# Temp_Board_1_2_2.net
KiCad netlist of a schematic drawn in EAGLE
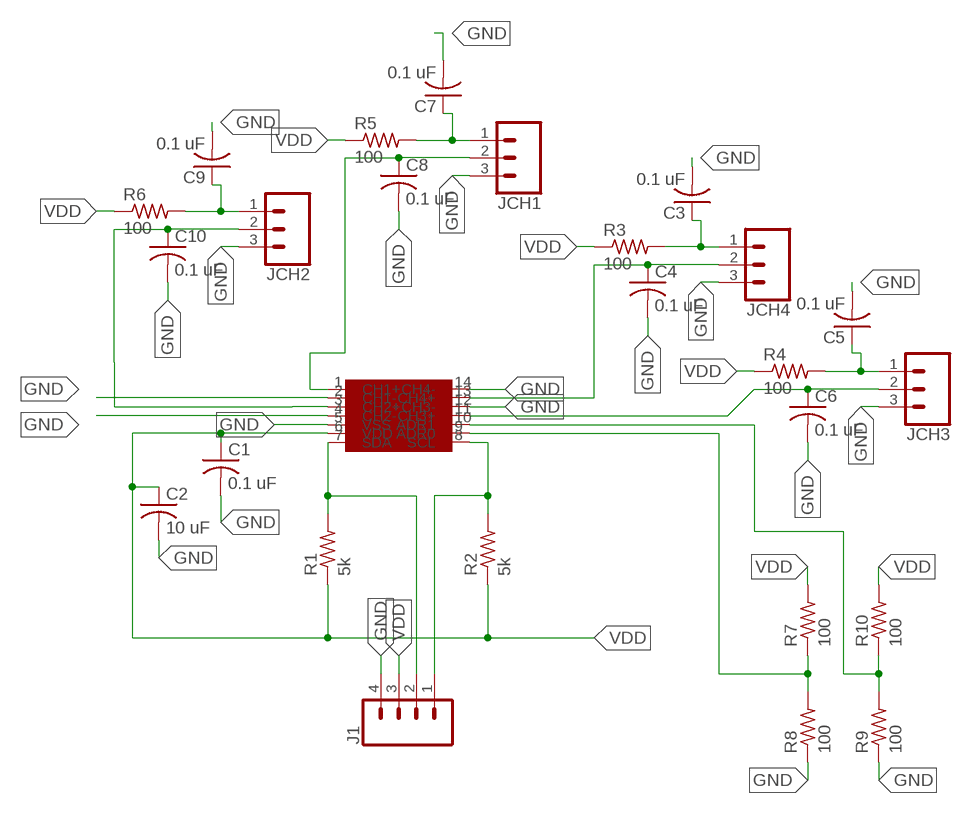
[diagram p0: schematic, sheet 1]

(export (version "E")
  (design (tool "Eeschema 10.0.6"))
  (components
    (comp (ref "C1")
      (value "0.1 uF")
      (footprint "eagle-import:C0805")
      (libsource (lib "eagle-import") (part "C-USC0805"))
    )
    (comp (ref "C2")
      (value "10 uF")
      (footprint "eagle-import:C0805")
      (libsource (lib "eagle-import") (part "C-USC0805"))
    )
    (comp (ref "C3")
      (value "0.1 uF")
      (footprint "eagle-import:C0805")
      (libsource (lib "eagle-import") (part "C-USC0805"))
    )
    (comp (ref "C4")
      (value "0.1 uF")
      (footprint "eagle-import:C0805")
      (libsource (lib "eagle-import") (part "C-USC0805"))
    )
    (comp (ref "C5")
      (value "0.1 uF")
      (footprint "eagle-import:C0805")
      (libsource (lib "eagle-import") (part "C-USC0805"))
    )
    (comp (ref "C6")
      (value "0.1 uF")
      (footprint "eagle-import:C0805")
      (libsource (lib "eagle-import") (part "C-USC0805"))
    )
    (comp (ref "C7")
      (value "0.1 uF")
      (footprint "eagle-import:C0805")
      (libsource (lib "eagle-import") (part "C-USC0805"))
    )
    (comp (ref "C8")
      (value "0.1 uF")
      (footprint "eagle-import:C0805")
      (libsource (lib "eagle-import") (part "C-USC0805"))
    )
    (comp (ref "C9")
      (value "0.1 uF")
      (footprint "eagle-import:C0805")
      (libsource (lib "eagle-import") (part "C-USC0805"))
    )
    (comp (ref "C10")
      (value "0.1 uF")
      (footprint "eagle-import:C0805")
      (libsource (lib "eagle-import") (part "C-USC0805"))
    )
    (comp (ref "J1")
      (value "CONN_04LOCK_LONGPADS")
      (footprint "eagle-import:1X04_LOCK_LONGPADS")
      (libsource (lib "eagle-import") (part "CONN_04LOCK_LONGPADS"))
    )
    (comp (ref "JCH1")
      (value "CONN_03LOCK_LONGPADS")
      (footprint "eagle-import:1X03_LOCK_LONGPADS")
      (libsource (lib "eagle-import") (part "CONN_03LOCK_LONGPADS"))
    )
    (comp (ref "JCH2")
      (value "CONN_03LOCK_LONGPADS")
      (footprint "eagle-import:1X03_LOCK_LONGPADS")
      (libsource (lib "eagle-import") (part "CONN_03LOCK_LONGPADS"))
    )
    (comp (ref "JCH3")
      (value "CONN_03LOCK_LONGPADS")
      (footprint "eagle-import:1X03_LOCK_LONGPADS")
      (libsource (lib "eagle-import") (part "CONN_03LOCK_LONGPADS"))
    )
    (comp (ref "JCH4")
      (value "CONN_03LOCK_LONGPADS")
      (footprint "eagle-import:1X03_LOCK_LONGPADS")
      (libsource (lib "eagle-import") (part "CONN_03LOCK_LONGPADS"))
    )
    (comp (ref "R1")
      (value "5k")
      (footprint "eagle-import:M0805")
      (libsource (lib "eagle-import") (part "R-US_M0805"))
    )
    (comp (ref "R2")
      (value "5k")
      (footprint "eagle-import:M0805")
      (libsource (lib "eagle-import") (part "R-US_M0805"))
    )
    (comp (ref "R3")
      (value "100")
      (footprint "eagle-import:M0805")
      (libsource (lib "eagle-import") (part "R-US_M0805"))
    )
    (comp (ref "R4")
      (value "100")
      (footprint "eagle-import:M0805")
      (libsource (lib "eagle-import") (part "R-US_M0805"))
    )
    (comp (ref "R5")
      (value "100")
      (footprint "eagle-import:M0805")
      (libsource (lib "eagle-import") (part "R-US_M0805"))
    )
    (comp (ref "R6")
      (value "100")
      (footprint "eagle-import:M0805")
      (libsource (lib "eagle-import") (part "R-US_M0805"))
    )
    (comp (ref "R7")
      (value "100")
      (footprint "eagle-import:M0805")
      (libsource (lib "eagle-import") (part "R-US_M0805"))
    )
    (comp (ref "R8")
      (value "100")
      (footprint "eagle-import:M0805")
      (libsource (lib "eagle-import") (part "R-US_M0805"))
    )
    (comp (ref "R9")
      (value "100")
      (footprint "eagle-import:M0805")
      (libsource (lib "eagle-import") (part "R-US_M0805"))
    )
    (comp (ref "R10")
      (value "100")
      (footprint "eagle-import:M0805")
      (libsource (lib "eagle-import") (part "R-US_M0805"))
    )
    (comp (ref "U$1")
      (value "MCP3428A")
      (footprint "eagle-import:C04-065B")
      (libsource (lib "eagle-import") (part "MCP3428A"))
    )
  )
  (nets
    (net (code "1") (name "GND") (class "Default")
      (node (ref "C1") (pin "2") (pinfunction "2_2") (pintype "passive"))
      (node (ref "C10") (pin "2") (pinfunction "2_2") (pintype "passive"))
      (node (ref "C2") (pin "2") (pinfunction "2_2") (pintype "passive"))
      (node (ref "C3") (pin "2") (pinfunction "2_2") (pintype "passive"))
      (node (ref "C4") (pin "2") (pinfunction "2_2") (pintype "passive"))
      (node (ref "C5") (pin "2") (pinfunction "2_2") (pintype "passive"))
      (node (ref "C6") (pin "2") (pinfunction "2_2") (pintype "passive"))
      (node (ref "C7") (pin "2") (pinfunction "2_2") (pintype "passive"))
      (node (ref "C8") (pin "2") (pinfunction "2_2") (pintype "passive"))
      (node (ref "C9") (pin "2") (pinfunction "2_2") (pintype "passive"))
      (node (ref "J1") (pin "4") (pinfunction "4_4") (pintype "passive"))
      (node (ref "JCH1") (pin "3") (pinfunction "3_3") (pintype "passive"))
      (node (ref "JCH2") (pin "3") (pinfunction "3_3") (pintype "passive"))
      (node (ref "JCH3") (pin "3") (pinfunction "3_3") (pintype "passive"))
      (node (ref "JCH4") (pin "3") (pinfunction "3_3") (pintype "passive"))
      (node (ref "R8") (pin "1") (pinfunction "1_1") (pintype "passive"))
      (node (ref "R9") (pin "1") (pinfunction "1_1") (pintype "passive"))
      (node (ref "U$1") (pin "12") (pinfunction "CH3-_12") (pintype "bidirectional"))
      (node (ref "U$1") (pin "14") (pinfunction "CH4-_14") (pintype "bidirectional"))
      (node (ref "U$1") (pin "2") (pinfunction "CH1-_2") (pintype "bidirectional"))
      (node (ref "U$1") (pin "4") (pinfunction "CH2-_4") (pintype "bidirectional"))
      (node (ref "U$1") (pin "5") (pinfunction "VSS_5") (pintype "bidirectional"))
    )
    (net (code "2") (name "Net-(C3-Pad1)") (class "Default")
      (node (ref "C3") (pin "1") (pinfunction "1_1") (pintype "passive"))
      (node (ref "JCH4") (pin "1") (pinfunction "1_1") (pintype "passive"))
      (node (ref "R3") (pin "2") (pinfunction "2_2") (pintype "passive"))
    )
    (net (code "3") (name "Net-(C5-Pad1)") (class "Default")
      (node (ref "C5") (pin "1") (pinfunction "1_1") (pintype "passive"))
      (node (ref "JCH3") (pin "1") (pinfunction "1_1") (pintype "passive"))
      (node (ref "R4") (pin "2") (pinfunction "2_2") (pintype "passive"))
    )
    (net (code "4") (name "Net-(C7-Pad1)") (class "Default")
      (node (ref "C7") (pin "1") (pinfunction "1_1") (pintype "passive"))
      (node (ref "JCH1") (pin "1") (pinfunction "1_1") (pintype "passive"))
      (node (ref "R5") (pin "2") (pinfunction "2_2") (pintype "passive"))
    )
    (net (code "5") (name "Net-(C9-Pad1)") (class "Default")
      (node (ref "C9") (pin "1") (pinfunction "1_1") (pintype "passive"))
      (node (ref "JCH2") (pin "1") (pinfunction "1_1") (pintype "passive"))
      (node (ref "R6") (pin "2") (pinfunction "2_2") (pintype "passive"))
    )
    (net (code "6") (name "Net-(U$1-ADR0)") (class "Default")
      (node (ref "R7") (pin "1") (pinfunction "1_1") (pintype "passive"))
      (node (ref "R8") (pin "2") (pinfunction "2_2") (pintype "passive"))
      (node (ref "U$1") (pin "9") (pinfunction "ADR0_9") (pintype "bidirectional"))
    )
    (net (code "7") (name "Net-(U$1-ADR1)") (class "Default")
      (node (ref "R10") (pin "1") (pinfunction "1_1") (pintype "passive"))
      (node (ref "R9") (pin "2") (pinfunction "2_2") (pintype "passive"))
      (node (ref "U$1") (pin "10") (pinfunction "ADR1_10") (pintype "bidirectional"))
    )
    (net (code "8") (name "Net-(U$1-CH1+)") (class "Default")
      (node (ref "C8") (pin "1") (pinfunction "1_1") (pintype "passive"))
      (node (ref "JCH1") (pin "2") (pinfunction "2_2") (pintype "passive"))
      (node (ref "U$1") (pin "1") (pinfunction "CH1+_1") (pintype "bidirectional"))
    )
    (net (code "9") (name "Net-(U$1-CH2+)") (class "Default")
      (node (ref "C10") (pin "1") (pinfunction "1_1") (pintype "passive"))
      (node (ref "JCH2") (pin "2") (pinfunction "2_2") (pintype "passive"))
      (node (ref "U$1") (pin "3") (pinfunction "CH2+_3") (pintype "bidirectional"))
    )
    (net (code "10") (name "Net-(U$1-CH3+)") (class "Default")
      (node (ref "C6") (pin "1") (pinfunction "1_1") (pintype "passive"))
      (node (ref "JCH3") (pin "2") (pinfunction "2_2") (pintype "passive"))
      (node (ref "U$1") (pin "11") (pinfunction "CH3+_11") (pintype "bidirectional"))
    )
    (net (code "11") (name "Net-(U$1-CH4+)") (class "Default")
      (node (ref "C4") (pin "1") (pinfunction "1_1") (pintype "passive"))
      (node (ref "JCH4") (pin "2") (pinfunction "2_2") (pintype "passive"))
      (node (ref "U$1") (pin "13") (pinfunction "CH4+_13") (pintype "bidirectional"))
    )
    (net (code "12") (name "Net-(U$1-SCL)") (class "Default")
      (node (ref "J1") (pin "1") (pinfunction "1_1") (pintype "passive"))
      (node (ref "R2") (pin "2") (pinfunction "2_2") (pintype "passive"))
      (node (ref "U$1") (pin "8") (pinfunction "SCL_8") (pintype "bidirectional"))
    )
    (net (code "13") (name "Net-(U$1-SDA)") (class "Default")
      (node (ref "J1") (pin "2") (pinfunction "2_2") (pintype "passive"))
      (node (ref "R1") (pin "2") (pinfunction "2_2") (pintype "passive"))
      (node (ref "U$1") (pin "7") (pinfunction "SDA_7") (pintype "bidirectional"))
    )
    (net (code "14") (name "VDD") (class "Default")
      (node (ref "C1") (pin "1") (pinfunction "1_1") (pintype "passive"))
      (node (ref "C2") (pin "1") (pinfunction "1_1") (pintype "passive"))
      (node (ref "J1") (pin "3") (pinfunction "3_3") (pintype "passive"))
      (node (ref "R1") (pin "1") (pinfunction "1_1") (pintype "passive"))
      (node (ref "R10") (pin "2") (pinfunction "2_2") (pintype "passive"))
      (node (ref "R2") (pin "1") (pinfunction "1_1") (pintype "passive"))
      (node (ref "R3") (pin "1") (pinfunction "1_1") (pintype "passive"))
      (node (ref "R4") (pin "1") (pinfunction "1_1") (pintype "passive"))
      (node (ref "R5") (pin "1") (pinfunction "1_1") (pintype "passive"))
      (node (ref "R6") (pin "1") (pinfunction "1_1") (pintype "passive"))
      (node (ref "R7") (pin "2") (pinfunction "2_2") (pintype "passive"))
      (node (ref "U$1") (pin "6") (pinfunction "VDD_6") (pintype "bidirectional"))
    )
  )
)
